# Sheet1.net
KiCad netlist of a schematic drawn in Altium Designer
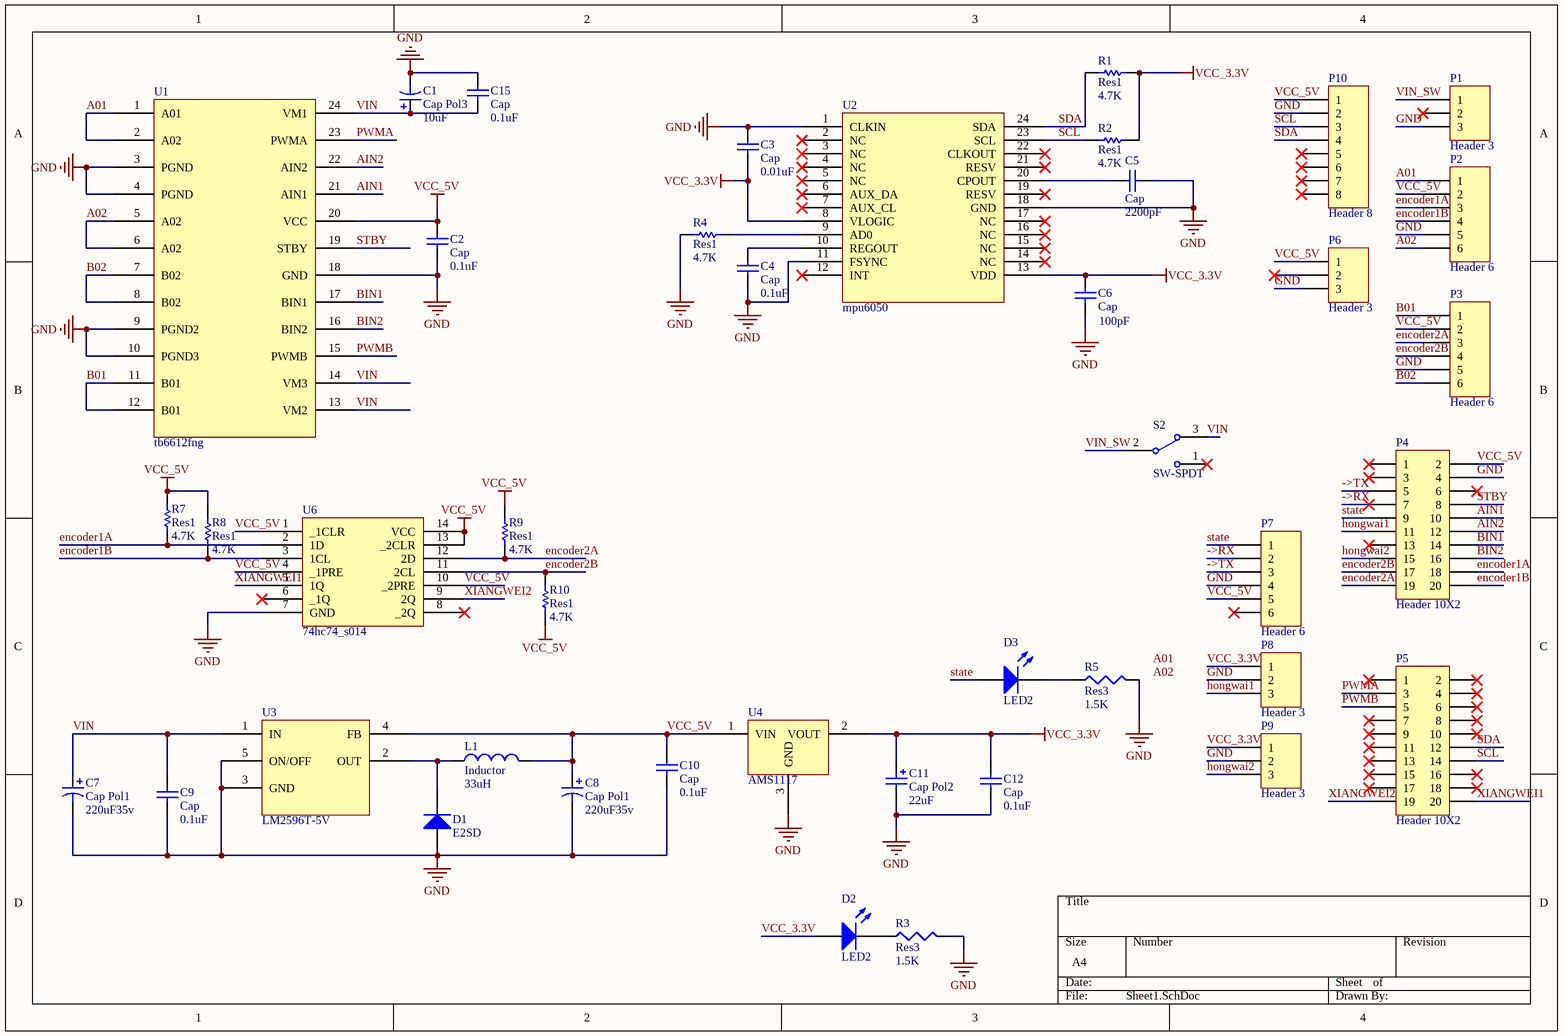
[diagram p0: Sheet1.SchDoc]

(export (version "E")
  (design (tool "Eeschema 10.0.6"))
  (components
    (comp (ref "C1")
      (value "Cap Pol3")
      (footprint "CAP POL-SMD-B")
      (description "Polarized Capacitor (Surface Mount)")
      (fields (field (name "ALTIUM_VALUE") "10uF") (field (name "PUBLISHER") "Altium Limited"))
      (libsource (lib "Miscellaneous Devices") (part "Cap Pol3"))
    )
    (comp (ref "C2")
      (value "Cap")
      (footprint "CAP-0805-手工焊接")
      (description "Capacitor")
      (fields (field (name "ALTIUM_VALUE") "0.1uF") (field (name "PUBLISHER") "Altium Limited"))
      (libsource (lib "Miscellaneous Devices") (part "Cap"))
    )
    (comp (ref "C3")
      (value "Cap")
      (footprint "CAP-0805-手工焊接")
      (description "Capacitor")
      (fields (field (name "ALTIUM_VALUE") "0.01uF") (field (name "PUBLISHER") "Altium Limited"))
      (libsource (lib "Miscellaneous Devices") (part "Cap"))
    )
    (comp (ref "C4")
      (value "Cap")
      (footprint "CAP-0805-手工焊接")
      (description "Capacitor")
      (fields (field (name "ALTIUM_VALUE") "0.1uF") (field (name "PUBLISHER") "Altium Limited"))
      (libsource (lib "Miscellaneous Devices") (part "Cap"))
    )
    (comp (ref "C5")
      (value "Cap")
      (footprint "CAP-0805-手工焊接")
      (description "Capacitor")
      (fields (field (name "ALTIUM_VALUE") "2200pF") (field (name "PUBLISHER") "Altium Limited"))
      (libsource (lib "Miscellaneous Devices") (part "Cap"))
    )
    (comp (ref "C6")
      (value "Cap")
      (footprint "CAP-0805-手工焊接")
      (description "Capacitor")
      (fields (field (name "ALTIUM_VALUE") "100pF") (field (name "PUBLISHER") "Altium Limited"))
      (libsource (lib "Miscellaneous Devices") (part "Cap"))
    )
    (comp (ref "C7")
      (value "Cap Pol1")
      (footprint "C_SMD(8x10.3)")
      (description "Polarized Capacitor (Radial)")
      (fields (field (name "ALTIUM_VALUE") "220uF35v") (field (name "PUBLISHER") "Altium Limited"))
      (libsource (lib "Miscellaneous Devices") (part "Cap Pol1"))
    )
    (comp (ref "C8")
      (value "Cap Pol1")
      (footprint "C_SMD(8x10.3)")
      (description "Polarized Capacitor (Radial)")
      (fields (field (name "ALTIUM_VALUE") "220uF35v") (field (name "PUBLISHER") "Altium Limited"))
      (libsource (lib "Miscellaneous Devices") (part "Cap Pol1"))
    )
    (comp (ref "C9")
      (value "Cap")
      (footprint "CAP-0805-手工焊接")
      (description "Capacitor")
      (fields (field (name "ALTIUM_VALUE") "0.1uF") (field (name "PUBLISHER") "Altium Limited"))
      (libsource (lib "Miscellaneous Devices") (part "Cap"))
    )
    (comp (ref "C10")
      (value "Cap")
      (footprint "CAP-0805-手工焊接")
      (description "Capacitor")
      (fields (field (name "ALTIUM_VALUE") "0.1uF") (field (name "PUBLISHER") "Altium Limited"))
      (libsource (lib "Miscellaneous Devices") (part "Cap"))
    )
    (comp (ref "C11")
      (value "Cap Pol2")
      (footprint "CAP POL-SMD-B")
      (description "Polarized Capacitor (Axial)")
      (fields (field (name "ALTIUM_VALUE") "22uF") (field (name "PUBLISHER") "Altium Limited"))
      (libsource (lib "Miscellaneous Devices") (part "Cap Pol2"))
    )
    (comp (ref "C12")
      (value "Cap")
      (footprint "CAP-0805-手工焊接")
      (description "Capacitor")
      (fields (field (name "ALTIUM_VALUE") "0.1uF") (field (name "PUBLISHER") "Altium Limited"))
      (libsource (lib "Miscellaneous Devices") (part "Cap"))
    )
    (comp (ref "C15")
      (value "Cap")
      (footprint "CAP-0805-手工焊接")
      (description "Capacitor")
      (fields (field (name "ALTIUM_VALUE") "0.1uF") (field (name "PUBLISHER") "Altium Limited"))
      (libsource (lib "Miscellaneous Devices") (part "Cap"))
    )
    (comp (ref "D1")
      (value "E2SD")
      (footprint "SMA")
      (description "Default Diode")
      (fields (field (name "PUBLISHER") "Altium Limited"))
      (libsource (lib "Miscellaneous Devices") (part "Diode"))
    )
    (comp (ref "D2")
      (value "LED2")
      (footprint "LED-0805-手工焊接")
      (description "Typical RED, GREEN, YELLOW, AMBER GaAs LED")
      (fields (field (name "PUBLISHER") "Altium Limited"))
      (libsource (lib "Miscellaneous Devices") (part "LED2"))
    )
    (comp (ref "D3")
      (value "LED2")
      (footprint "LED-0805-手工焊接")
      (description "Typical RED, GREEN, YELLOW, AMBER GaAs LED")
      (fields (field (name "PUBLISHER") "Altium Limited"))
      (libsource (lib "Miscellaneous Devices") (part "LED2"))
    )
    (comp (ref "L1")
      (value "Inductor")
      (footprint "CDRH127")
      (fields (field (name "ALTIUM_VALUE") "33uH") (field (name "PUBLISHER") "Altium Limited"))
      (libsource (lib "Miscellaneous Devices") (part "Inductor"))
    )
    (comp (ref "P1")
      (value "Header 3")
      (footprint "HDR1X3")
      (description "Header, 3-Pin")
      (fields (field (name "PUBLISHER") "Altium Limited"))
      (libsource (lib "Miscellaneous Connectors") (part "Header 3"))
    )
    (comp (ref "P2")
      (value "Header 6")
      (footprint "PH2.0 6P")
      (description "Header, 6-Pin")
      (fields (field (name "PUBLISHER") "Altium Limited"))
      (libsource (lib "Miscellaneous Connectors") (part "Header 6"))
    )
    (comp (ref "P3")
      (value "Header 6")
      (footprint "PH2.0 6P")
      (description "Header, 6-Pin")
      (fields (field (name "PUBLISHER") "Altium Limited"))
      (libsource (lib "Miscellaneous Connectors") (part "Header 6"))
    )
    (comp (ref "P4")
      (value "Header 10X2")
      (footprint "HDR2X10 - duplicate")
      (description "Header, 10-Pin, Dual row")
      (fields (field (name "PUBLISHER") "Altium Limited"))
      (libsource (lib "Miscellaneous Connectors") (part "Header 10X2"))
    )
    (comp (ref "P5")
      (value "Header 10X2")
      (footprint "HDR2X10 - duplicate")
      (description "Header, 10-Pin, Dual row")
      (fields (field (name "PUBLISHER") "Altium Limited"))
      (libsource (lib "Miscellaneous Connectors") (part "Header 10X2"))
    )
    (comp (ref "P6")
      (value "Header 3")
      (footprint "HDR1X3")
      (description "Header, 3-Pin")
      (fields (field (name "PUBLISHER") "Altium Limited"))
      (libsource (lib "Miscellaneous Connectors") (part "Header 3"))
    )
    (comp (ref "P7")
      (value "Header 6")
      (footprint "HC05 MODULE")
      (description "Header, 6-Pin")
      (fields (field (name "PUBLISHER") "Altium Limited"))
      (libsource (lib "Miscellaneous Connectors") (part "Header 6"))
    )
    (comp (ref "P8")
      (value "Header 3")
      (footprint "HDR1*3 no_edge")
      (description "Header, 3-Pin")
      (fields (field (name "PUBLISHER") "Altium Limited"))
      (libsource (lib "Miscellaneous Connectors") (part "Header 3"))
    )
    (comp (ref "P9")
      (value "Header 3")
      (footprint "HDR1*3 no_edge")
      (description "Header, 3-Pin")
      (fields (field (name "PUBLISHER") "Altium Limited"))
      (libsource (lib "Miscellaneous Connectors") (part "Header 3"))
    )
    (comp (ref "P10")
      (value "Header 8")
      (footprint "mpu6050 module")
      (description "Header, 8-Pin")
      (fields (field (name "PUBLISHER") "Altium Limited"))
      (libsource (lib "Miscellaneous Connectors") (part "Header 8"))
    )
    (comp (ref "R1")
      (value "Res1")
      (footprint "RES-0805_手工焊接")
      (description "Resistor")
      (fields (field (name "ALTIUM_VALUE") "4.7K") (field (name "PUBLISHER") "Altium Limited"))
      (libsource (lib "Miscellaneous Devices") (part "Res1"))
    )
    (comp (ref "R2")
      (value "Res1")
      (footprint "RES-0805_手工焊接")
      (description "Resistor")
      (fields (field (name "ALTIUM_VALUE") "4.7K") (field (name "PUBLISHER") "Altium Limited"))
      (libsource (lib "Miscellaneous Devices") (part "Res1"))
    )
    (comp (ref "R3")
      (value "Res3")
      (footprint "RES-0805_手工焊接")
      (description "Resistor")
      (fields (field (name "ALTIUM_VALUE") "1.5K") (field (name "PUBLISHER") "Altium Limited"))
      (libsource (lib "Miscellaneous Devices") (part "Res3"))
    )
    (comp (ref "R4")
      (value "Res1")
      (footprint "RES-0805_手工焊接")
      (description "Resistor")
      (fields (field (name "ALTIUM_VALUE") "4.7K") (field (name "PUBLISHER") "Altium Limited"))
      (libsource (lib "Miscellaneous Devices") (part "Res1"))
    )
    (comp (ref "R5")
      (value "Res3")
      (footprint "RES-0805_手工焊接")
      (description "Resistor")
      (fields (field (name "ALTIUM_VALUE") "1.5K") (field (name "PUBLISHER") "Altium Limited"))
      (libsource (lib "Miscellaneous Devices") (part "Res3"))
    )
    (comp (ref "R7")
      (value "Res1")
      (footprint "RES-0805_手工焊接")
      (description "Resistor")
      (fields (field (name "ALTIUM_VALUE") "4.7K") (field (name "PUBLISHER") "Altium Limited"))
      (libsource (lib "Miscellaneous Devices") (part "Res1"))
    )
    (comp (ref "R8")
      (value "Res1")
      (footprint "RES-0805_手工焊接")
      (description "Resistor")
      (fields (field (name "ALTIUM_VALUE") "4.7K") (field (name "PUBLISHER") "Altium Limited"))
      (libsource (lib "Miscellaneous Devices") (part "Res1"))
    )
    (comp (ref "R9")
      (value "Res1")
      (footprint "RES-0805_手工焊接")
      (description "Resistor")
      (fields (field (name "ALTIUM_VALUE") "4.7K") (field (name "PUBLISHER") "Altium Limited"))
      (libsource (lib "Miscellaneous Devices") (part "Res1"))
    )
    (comp (ref "R10")
      (value "Res1")
      (footprint "RES-0805_手工焊接")
      (description "Resistor")
      (fields (field (name "ALTIUM_VALUE") "4.7K") (field (name "PUBLISHER") "Altium Limited"))
      (libsource (lib "Miscellaneous Devices") (part "Res1"))
    )
    (comp (ref "S2")
      (value "SW-SPDT")
      (footprint "ss12d10")
      (description "SPDT Subminiature Toggle Switch, Right Angle Mounting, Vertical Actuation")
      (fields (field (name "PUBLISHER") "Altium Limited"))
      (libsource (lib "Miscellaneous Devices") (part "SW-SPDT"))
    )
    (comp (ref "U1")
      (value "tb6612fng")
      (footprint "tb6612fng - duplicate")
      (libsource (lib "Schlib1") (part "tb6612fng"))
    )
    (comp (ref "U2") (value "mpu6050") (footprint "QFN-24") (libsource (lib "Schlib1") (part "mpu6050")))
    (comp (ref "U3")
      (value "LM2596T-5V")
      (footprint "TO-263-5 - TYPE1")
      (libsource (lib "Schlib1") (part "LM2596T-5V"))
    )
    (comp (ref "U4") (value "AMS1117") (footprint "SOT-223") (libsource (lib "Schlib1") (part "AMS1117")))
    (comp (ref "U6")
      (value "74hc74_s014")
      (footprint "74HC74D_SOP14")
      (libsource (lib "Schlib1") (part "74hc74_s014"))
    )
  )
  (nets
    (net (code "1") (name "/->RX") (class "Default")
      (node (ref "P4") (pin "7") (pinfunction "7_7") (pintype "passive"))
      (node (ref "P7") (pin "2") (pinfunction "2_2") (pintype "passive"))
    )
    (net (code "2") (name "/->TX") (class "Default")
      (node (ref "P4") (pin "5") (pinfunction "5_5") (pintype "passive"))
      (node (ref "P7") (pin "3") (pinfunction "3_3") (pintype "passive"))
    )
    (net (code "3") (name "/A01") (class "Default")
      (node (ref "P2") (pin "1") (pinfunction "1_1") (pintype "passive"))
      (node (ref "U1") (pin "1") (pinfunction "A01_1") (pintype "passive"))
      (node (ref "U1") (pin "2") (pinfunction "A02_2") (pintype "passive"))
    )
    (net (code "4") (name "/A02") (class "Default")
      (node (ref "P2") (pin "6") (pinfunction "6_6") (pintype "passive"))
      (node (ref "U1") (pin "5") (pinfunction "A02_5") (pintype "passive"))
      (node (ref "U1") (pin "6") (pinfunction "A02_6") (pintype "passive"))
    )
    (net (code "5") (name "/AIN1") (class "Default")
      (node (ref "P4") (pin "10") (pinfunction "10_10") (pintype "passive"))
      (node (ref "U1") (pin "21") (pinfunction "AIN1_21") (pintype "passive"))
    )
    (net (code "6") (name "/AIN2") (class "Default")
      (node (ref "P4") (pin "12") (pinfunction "12_12") (pintype "passive"))
      (node (ref "U1") (pin "22") (pinfunction "AIN2_22") (pintype "passive"))
    )
    (net (code "7") (name "/B01") (class "Default")
      (node (ref "P3") (pin "1") (pinfunction "1_1") (pintype "passive"))
      (node (ref "U1") (pin "11") (pinfunction "B01_11") (pintype "passive"))
      (node (ref "U1") (pin "12") (pinfunction "B01_12") (pintype "passive"))
    )
    (net (code "8") (name "/B02") (class "Default")
      (node (ref "P3") (pin "6") (pinfunction "6_6") (pintype "passive"))
      (node (ref "U1") (pin "7") (pinfunction "B02_7") (pintype "passive"))
      (node (ref "U1") (pin "8") (pinfunction "B02_8") (pintype "passive"))
    )
    (net (code "9") (name "/BIN1") (class "Default")
      (node (ref "P4") (pin "14") (pinfunction "14_14") (pintype "passive"))
      (node (ref "U1") (pin "17") (pinfunction "BIN1_17") (pintype "passive"))
    )
    (net (code "10") (name "/BIN2") (class "Default")
      (node (ref "P4") (pin "16") (pinfunction "16_16") (pintype "passive"))
      (node (ref "U1") (pin "16") (pinfunction "BIN2_16") (pintype "passive"))
    )
    (net (code "11") (name "/PWMA") (class "Default")
      (node (ref "P5") (pin "3") (pinfunction "3_3") (pintype "passive"))
      (node (ref "U1") (pin "23") (pinfunction "PWMA_23") (pintype "passive"))
    )
    (net (code "12") (name "/PWMB") (class "Default")
      (node (ref "P5") (pin "5") (pinfunction "5_5") (pintype "passive"))
      (node (ref "U1") (pin "15") (pinfunction "PWMB_15") (pintype "passive"))
    )
    (net (code "13") (name "/SCL") (class "Default")
      (node (ref "P10") (pin "3") (pinfunction "3_3") (pintype "passive"))
      (node (ref "P5") (pin "14") (pinfunction "14_14") (pintype "passive"))
      (node (ref "R2") (pin "1") (pinfunction "1_1") (pintype "passive"))
      (node (ref "U2") (pin "23") (pinfunction "SCL_23") (pintype "passive"))
    )
    (net (code "14") (name "/SDA") (class "Default")
      (node (ref "P10") (pin "4") (pinfunction "4_4") (pintype "passive"))
      (node (ref "P5") (pin "12") (pinfunction "12_12") (pintype "passive"))
      (node (ref "R1") (pin "1") (pinfunction "1_1") (pintype "passive"))
      (node (ref "U2") (pin "24") (pinfunction "SDA_24") (pintype "passive"))
    )
    (net (code "15") (name "/STBY") (class "Default")
      (node (ref "P4") (pin "8") (pinfunction "8_8") (pintype "passive"))
      (node (ref "U1") (pin "19") (pinfunction "STBY_19") (pintype "passive"))
    )
    (net (code "16") (name "/VIN") (class "Default")
      (node (ref "C1") (pin "1") (pinfunction "1_1") (pintype "passive"))
      (node (ref "C15") (pin "1") (pinfunction "1_1") (pintype "passive"))
      (node (ref "C7") (pin "1") (pinfunction "1_1") (pintype "passive"))
      (node (ref "C9") (pin "2") (pinfunction "2_2") (pintype "passive"))
      (node (ref "S2") (pin "3") (pinfunction "3_3") (pintype "passive"))
      (node (ref "U1") (pin "13") (pinfunction "VM2_13") (pintype "passive"))
      (node (ref "U1") (pin "14") (pinfunction "VM3_14") (pintype "passive"))
      (node (ref "U1") (pin "24") (pinfunction "VM1_24") (pintype "passive"))
      (node (ref "U3") (pin "1") (pinfunction "IN_1") (pintype "passive"))
    )
    (net (code "17") (name "/VIN_SW") (class "Default")
      (node (ref "P1") (pin "1") (pinfunction "1_1") (pintype "passive"))
      (node (ref "S2") (pin "2") (pinfunction "2_2") (pintype "passive"))
    )
    (net (code "18") (name "/XIANGWEI1") (class "Default")
      (node (ref "P5") (pin "20") (pinfunction "20_20") (pintype "passive"))
      (node (ref "U6") (pin "5") (pinfunction "1Q_5") (pintype "passive"))
    )
    (net (code "19") (name "/XIANGWEI2") (class "Default")
      (node (ref "P5") (pin "19") (pinfunction "19_19") (pintype "passive"))
      (node (ref "U6") (pin "9") (pinfunction "2Q_9") (pintype "passive"))
    )
    (net (code "20") (name "/encoder1A") (class "Default")
      (node (ref "P2") (pin "3") (pinfunction "3_3") (pintype "passive"))
      (node (ref "P4") (pin "18") (pinfunction "18_18") (pintype "passive"))
      (node (ref "R7") (pin "2") (pinfunction "2_2") (pintype "passive"))
      (node (ref "U6") (pin "2") (pinfunction "1D_2") (pintype "passive"))
    )
    (net (code "21") (name "/encoder1B") (class "Default")
      (node (ref "P2") (pin "4") (pinfunction "4_4") (pintype "passive"))
      (node (ref "P4") (pin "20") (pinfunction "20_20") (pintype "passive"))
      (node (ref "R8") (pin "2") (pinfunction "2_2") (pintype "passive"))
      (node (ref "U6") (pin "3") (pinfunction "1CL_3") (pintype "passive"))
    )
    (net (code "22") (name "/encoder2A") (class "Default")
      (node (ref "P3") (pin "3") (pinfunction "3_3") (pintype "passive"))
      (node (ref "P4") (pin "19") (pinfunction "19_19") (pintype "passive"))
      (node (ref "R9") (pin "2") (pinfunction "2_2") (pintype "passive"))
      (node (ref "U6") (pin "12") (pinfunction "2D_12") (pintype "passive"))
    )
    (net (code "23") (name "/encoder2B") (class "Default")
      (node (ref "P3") (pin "4") (pinfunction "4_4") (pintype "passive"))
      (node (ref "P4") (pin "17") (pinfunction "17_17") (pintype "passive"))
      (node (ref "R10") (pin "1") (pinfunction "1_1") (pintype "passive"))
      (node (ref "U6") (pin "11") (pinfunction "2CL_11") (pintype "passive"))
    )
    (net (code "24") (name "/hongwai1") (class "Default")
      (node (ref "P4") (pin "11") (pinfunction "11_11") (pintype "passive"))
      (node (ref "P8") (pin "3") (pinfunction "3_3") (pintype "passive"))
    )
    (net (code "25") (name "/hongwai2") (class "Default")
      (node (ref "P4") (pin "15") (pinfunction "15_15") (pintype "passive"))
      (node (ref "P9") (pin "3") (pinfunction "3_3") (pintype "passive"))
    )
    (net (code "26") (name "/state") (class "Default")
      (node (ref "D3") (pin "1") (pinfunction "A_1") (pintype "passive"))
      (node (ref "P4") (pin "9") (pinfunction "9_9") (pintype "passive"))
      (node (ref "P7") (pin "1") (pinfunction "1_1") (pintype "passive"))
    )
    (net (code "27") (name "GND") (class "Default")
      (node (ref "C1") (pin "2") (pinfunction "2_2") (pintype "passive"))
      (node (ref "C10") (pin "1") (pinfunction "1_1") (pintype "passive"))
      (node (ref "C11") (pin "2") (pinfunction "2_2") (pintype "passive"))
      (node (ref "C12") (pin "1") (pinfunction "1_1") (pintype "passive"))
      (node (ref "C15") (pin "2") (pinfunction "2_2") (pintype "passive"))
      (node (ref "C2") (pin "1") (pinfunction "1_1") (pintype "passive"))
      (node (ref "C3") (pin "2") (pinfunction "2_2") (pintype "passive"))
      (node (ref "C4") (pin "1") (pinfunction "1_1") (pintype "passive"))
      (node (ref "C5") (pin "1") (pinfunction "1_1") (pintype "passive"))
      (node (ref "C6") (pin "1") (pinfunction "1_1") (pintype "passive"))
      (node (ref "C7") (pin "2") (pinfunction "2_2") (pintype "passive"))
      (node (ref "C8") (pin "2") (pinfunction "2_2") (pintype "passive"))
      (node (ref "C9") (pin "1") (pinfunction "1_1") (pintype "passive"))
      (node (ref "D1") (pin "1") (pinfunction "A_1") (pintype "passive"))
      (node (ref "P1") (pin "3") (pinfunction "3_3") (pintype "passive"))
      (node (ref "P10") (pin "2") (pinfunction "2_2") (pintype "passive"))
      (node (ref "P2") (pin "5") (pinfunction "5_5") (pintype "passive"))
      (node (ref "P3") (pin "5") (pinfunction "5_5") (pintype "passive"))
      (node (ref "P4") (pin "4") (pinfunction "4_4") (pintype "passive"))
      (node (ref "P6") (pin "3") (pinfunction "3_3") (pintype "passive"))
      (node (ref "P7") (pin "4") (pinfunction "4_4") (pintype "passive"))
      (node (ref "P8") (pin "2") (pinfunction "2_2") (pintype "passive"))
      (node (ref "P9") (pin "2") (pinfunction "2_2") (pintype "passive"))
      (node (ref "R3") (pin "2") (pinfunction "2_2") (pintype "passive"))
      (node (ref "R4") (pin "1") (pinfunction "1_1") (pintype "passive"))
      (node (ref "R5") (pin "2") (pinfunction "2_2") (pintype "passive"))
      (node (ref "U1") (pin "10") (pinfunction "PGND3_10") (pintype "passive"))
      (node (ref "U1") (pin "18") (pinfunction "GND_18") (pintype "passive"))
      (node (ref "U1") (pin "3") (pinfunction "PGND_3") (pintype "passive"))
      (node (ref "U1") (pin "4") (pinfunction "PGND_4") (pintype "passive"))
      (node (ref "U1") (pin "9") (pinfunction "PGND2_9") (pintype "passive"))
      (node (ref "U2") (pin "1") (pinfunction "CLKIN_1") (pintype "passive"))
      (node (ref "U2") (pin "11") (pinfunction "FSYNC_11") (pintype "passive"))
      (node (ref "U2") (pin "18") (pinfunction "GND_18") (pintype "passive"))
      (node (ref "U3") (pin "3") (pinfunction "GND_3") (pintype "passive"))
      (node (ref "U3") (pin "5") (pinfunction "ON/OFF_5") (pintype "passive"))
      (node (ref "U4") (pin "3") (pinfunction "GND_3") (pintype "passive"))
      (node (ref "U6") (pin "7") (pinfunction "GND_7") (pintype "passive"))
    )
    (net (code "28") (name "Net-(D1-K)") (class "Default")
      (node (ref "D1") (pin "2") (pinfunction "K_2") (pintype "passive"))
      (node (ref "L1") (pin "1") (pinfunction "1_1") (pintype "passive"))
      (node (ref "U3") (pin "2") (pinfunction "OUT_2") (pintype "passive"))
    )
    (net (code "29") (name "Net-(D2-K)") (class "Default")
      (node (ref "D2") (pin "2") (pinfunction "K_2") (pintype "passive"))
      (node (ref "R3") (pin "1") (pinfunction "1_1") (pintype "passive"))
    )
    (net (code "30") (name "Net-(D3-K)") (class "Default")
      (node (ref "D3") (pin "2") (pinfunction "K_2") (pintype "passive"))
      (node (ref "R5") (pin "1") (pinfunction "1_1") (pintype "passive"))
    )
    (net (code "31") (name "Net-(U2-AD0)") (class "Default")
      (node (ref "R4") (pin "2") (pinfunction "2_2") (pintype "passive"))
      (node (ref "U2") (pin "9") (pinfunction "AD0_9") (pintype "passive"))
    )
    (net (code "32") (name "Net-(U2-CPOUT)") (class "Default")
      (node (ref "C5") (pin "2") (pinfunction "2_2") (pintype "passive"))
      (node (ref "U2") (pin "20") (pinfunction "CPOUT_20") (pintype "passive"))
    )
    (net (code "33") (name "Net-(U2-REGOUT)") (class "Default")
      (node (ref "C4") (pin "2") (pinfunction "2_2") (pintype "passive"))
      (node (ref "U2") (pin "10") (pinfunction "REGOUT_10") (pintype "passive"))
    )
    (net (code "34") (name "VCC_3.3V") (class "Default")
      (node (ref "C11") (pin "1") (pinfunction "1_1") (pintype "passive"))
      (node (ref "C12") (pin "2") (pinfunction "2_2") (pintype "passive"))
      (node (ref "C3") (pin "1") (pinfunction "1_1") (pintype "passive"))
      (node (ref "C6") (pin "2") (pinfunction "2_2") (pintype "passive"))
      (node (ref "D2") (pin "1") (pinfunction "A_1") (pintype "passive"))
      (node (ref "P8") (pin "1") (pinfunction "1_1") (pintype "passive"))
      (node (ref "P9") (pin "1") (pinfunction "1_1") (pintype "passive"))
      (node (ref "R1") (pin "2") (pinfunction "2_2") (pintype "passive"))
      (node (ref "R2") (pin "2") (pinfunction "2_2") (pintype "passive"))
      (node (ref "U2") (pin "13") (pinfunction "VDD_13") (pintype "passive"))
      (node (ref "U2") (pin "8") (pinfunction "VLOGIC_8") (pintype "passive"))
      (node (ref "U4") (pin "2") (pinfunction "VOUT_2") (pintype "passive"))
    )
    (net (code "35") (name "VCC_5V") (class "Default")
      (node (ref "C10") (pin "2") (pinfunction "2_2") (pintype "passive"))
      (node (ref "C2") (pin "2") (pinfunction "2_2") (pintype "passive"))
      (node (ref "C8") (pin "1") (pinfunction "1_1") (pintype "passive"))
      (node (ref "L1") (pin "2") (pinfunction "2_2") (pintype "passive"))
      (node (ref "P10") (pin "1") (pinfunction "1_1") (pintype "passive"))
      (node (ref "P2") (pin "2") (pinfunction "2_2") (pintype "passive"))
      (node (ref "P3") (pin "2") (pinfunction "2_2") (pintype "passive"))
      (node (ref "P4") (pin "2") (pinfunction "2_2") (pintype "passive"))
      (node (ref "P6") (pin "1") (pinfunction "1_1") (pintype "passive"))
      (node (ref "P7") (pin "5") (pinfunction "5_5") (pintype "passive"))
      (node (ref "R10") (pin "2") (pinfunction "2_2") (pintype "passive"))
      (node (ref "R7") (pin "1") (pinfunction "1_1") (pintype "passive"))
      (node (ref "R8") (pin "1") (pinfunction "1_1") (pintype "passive"))
      (node (ref "R9") (pin "1") (pinfunction "1_1") (pintype "passive"))
      (node (ref "U1") (pin "20") (pinfunction "VCC_20") (pintype "passive"))
      (node (ref "U3") (pin "4") (pinfunction "FB_4") (pintype "passive"))
      (node (ref "U4") (pin "1") (pinfunction "VIN_1") (pintype "passive"))
      (node (ref "U6") (pin "1") (pinfunction "_1CLR_1") (pintype "passive"))
      (node (ref "U6") (pin "10") (pinfunction "_2PRE_10") (pintype "passive"))
      (node (ref "U6") (pin "13") (pinfunction "_2CLR_13") (pintype "passive"))
      (node (ref "U6") (pin "14") (pinfunction "VCC_14") (pintype "passive"))
      (node (ref "U6") (pin "4") (pinfunction "_1PRE_4") (pintype "passive"))
    )
    (net (code "36") (name "unconnected-(P1-Pad2)") (class "Default")
      (node (ref "P1") (pin "2") (pinfunction "2_2") (pintype "passive+no_connect"))
    )
    (net (code "37") (name "unconnected-(P4-Pad1)") (class "Default")
      (node (ref "P4") (pin "1") (pinfunction "1_1") (pintype "passive+no_connect"))
    )
    (net (code "38") (name "unconnected-(P4-Pad3)") (class "Default")
      (node (ref "P4") (pin "3") (pinfunction "3_3") (pintype "passive+no_connect"))
    )
    (net (code "39") (name "unconnected-(P4-Pad6)") (class "Default")
      (node (ref "P4") (pin "6") (pinfunction "6_6") (pintype "passive+no_connect"))
    )
    (net (code "40") (name "unconnected-(P4-Pad13)") (class "Default")
      (node (ref "P4") (pin "13") (pinfunction "13_13") (pintype "passive+no_connect"))
    )
    (net (code "41") (name "unconnected-(P5-Pad1)") (class "Default")
      (node (ref "P5") (pin "1") (pinfunction "1_1") (pintype "passive+no_connect"))
    )
    (net (code "42") (name "unconnected-(P5-Pad2)") (class "Default")
      (node (ref "P5") (pin "2") (pinfunction "2_2") (pintype "passive+no_connect"))
    )
    (net (code "43") (name "unconnected-(P5-Pad4)") (class "Default")
      (node (ref "P5") (pin "4") (pinfunction "4_4") (pintype "passive+no_connect"))
    )
    (net (code "44") (name "unconnected-(P5-Pad6)") (class "Default")
      (node (ref "P5") (pin "6") (pinfunction "6_6") (pintype "passive+no_connect"))
    )
    (net (code "45") (name "unconnected-(P5-Pad7)") (class "Default")
      (node (ref "P5") (pin "7") (pinfunction "7_7") (pintype "passive+no_connect"))
    )
    (net (code "46") (name "unconnected-(P5-Pad8)") (class "Default")
      (node (ref "P5") (pin "8") (pinfunction "8_8") (pintype "passive+no_connect"))
    )
    (net (code "47") (name "unconnected-(P5-Pad9)") (class "Default")
      (node (ref "P5") (pin "9") (pinfunction "9_9") (pintype "passive+no_connect"))
    )
    (net (code "48") (name "unconnected-(P5-Pad10)") (class "Default")
      (node (ref "P5") (pin "10") (pinfunction "10_10") (pintype "passive+no_connect"))
    )
    (net (code "49") (name "unconnected-(P5-Pad11)") (class "Default")
      (node (ref "P5") (pin "11") (pinfunction "11_11") (pintype "passive+no_connect"))
    )
    (net (code "50") (name "unconnected-(P5-Pad13)") (class "Default")
      (node (ref "P5") (pin "13") (pinfunction "13_13") (pintype "passive+no_connect"))
    )
    (net (code "51") (name "unconnected-(P5-Pad15)") (class "Default")
      (node (ref "P5") (pin "15") (pinfunction "15_15") (pintype "passive+no_connect"))
    )
    (net (code "52") (name "unconnected-(P5-Pad16)") (class "Default")
      (node (ref "P5") (pin "16") (pinfunction "16_16") (pintype "passive+no_connect"))
    )
    (net (code "53") (name "unconnected-(P5-Pad17)") (class "Default")
      (node (ref "P5") (pin "17") (pinfunction "17_17") (pintype "passive+no_connect"))
    )
    (net (code "54") (name "unconnected-(P5-Pad18)") (class "Default")
      (node (ref "P5") (pin "18") (pinfunction "18_18") (pintype "passive+no_connect"))
    )
    (net (code "55") (name "unconnected-(P6-Pad2)") (class "Default")
      (node (ref "P6") (pin "2") (pinfunction "2_2") (pintype "passive+no_connect"))
    )
    (net (code "56") (name "unconnected-(P7-Pad6)") (class "Default")
      (node (ref "P7") (pin "6") (pinfunction "6_6") (pintype "passive+no_connect"))
    )
    (net (code "57") (name "unconnected-(P10-Pad5)") (class "Default")
      (node (ref "P10") (pin "5") (pinfunction "5_5") (pintype "passive+no_connect"))
    )
    (net (code "58") (name "unconnected-(P10-Pad6)") (class "Default")
      (node (ref "P10") (pin "6") (pinfunction "6_6") (pintype "passive+no_connect"))
    )
    (net (code "59") (name "unconnected-(P10-Pad7)") (class "Default")
      (node (ref "P10") (pin "7") (pinfunction "7_7") (pintype "passive+no_connect"))
    )
    (net (code "60") (name "unconnected-(P10-Pad8)") (class "Default")
      (node (ref "P10") (pin "8") (pinfunction "8_8") (pintype "passive+no_connect"))
    )
    (net (code "61") (name "unconnected-(S2-Pad1)") (class "Default")
      (node (ref "S2") (pin "1") (pinfunction "1_1") (pintype "passive+no_connect"))
    )
    (net (code "62") (name "unconnected-(U2-AUX_CL-Pad7)") (class "Default")
      (node (ref "U2") (pin "7") (pinfunction "AUX_CL_7") (pintype "passive+no_connect"))
    )
    (net (code "63") (name "unconnected-(U2-AUX_DA-Pad6)") (class "Default")
      (node (ref "U2") (pin "6") (pinfunction "AUX_DA_6") (pintype "passive+no_connect"))
    )
    (net (code "64") (name "unconnected-(U2-CLKOUT-Pad22)") (class "Default")
      (node (ref "U2") (pin "22") (pinfunction "CLKOUT_22") (pintype "passive+no_connect"))
    )
    (net (code "65") (name "unconnected-(U2-INT-Pad12)") (class "Default")
      (node (ref "U2") (pin "12") (pinfunction "INT_12") (pintype "passive+no_connect"))
    )
    (net (code "66") (name "unconnected-(U2-NC-Pad2)") (class "Default")
      (node (ref "U2") (pin "2") (pinfunction "NC_2") (pintype "passive+no_connect"))
    )
    (net (code "67") (name "unconnected-(U2-NC-Pad3)") (class "Default")
      (node (ref "U2") (pin "3") (pinfunction "NC_3") (pintype "passive+no_connect"))
    )
    (net (code "68") (name "unconnected-(U2-NC-Pad4)") (class "Default")
      (node (ref "U2") (pin "4") (pinfunction "NC_4") (pintype "passive+no_connect"))
    )
    (net (code "69") (name "unconnected-(U2-NC-Pad5)") (class "Default")
      (node (ref "U2") (pin "5") (pinfunction "NC_5") (pintype "passive+no_connect"))
    )
    (net (code "70") (name "unconnected-(U2-NC-Pad14)") (class "Default")
      (node (ref "U2") (pin "14") (pinfunction "NC_14") (pintype "passive+no_connect"))
    )
    (net (code "71") (name "unconnected-(U2-NC-Pad15)") (class "Default")
      (node (ref "U2") (pin "15") (pinfunction "NC_15") (pintype "passive+no_connect"))
    )
    (net (code "72") (name "unconnected-(U2-NC-Pad16)") (class "Default")
      (node (ref "U2") (pin "16") (pinfunction "NC_16") (pintype "passive+no_connect"))
    )
    (net (code "73") (name "unconnected-(U2-NC-Pad17)") (class "Default")
      (node (ref "U2") (pin "17") (pinfunction "NC_17") (pintype "passive+no_connect"))
    )
    (net (code "74") (name "unconnected-(U2-RESV-Pad19)") (class "Default")
      (node (ref "U2") (pin "19") (pinfunction "RESV_19") (pintype "passive+no_connect"))
    )
    (net (code "75") (name "unconnected-(U2-RESV-Pad21)") (class "Default")
      (node (ref "U2") (pin "21") (pinfunction "RESV_21") (pintype "passive+no_connect"))
    )
    (net (code "76") (name "unconnected-(U6-_1Q-Pad6)") (class "Default")
      (node (ref "U6") (pin "6") (pinfunction "_1Q_6") (pintype "passive+no_connect"))
    )
    (net (code "77") (name "unconnected-(U6-_2Q-Pad8)") (class "Default")
      (node (ref "U6") (pin "8") (pinfunction "_2Q_8") (pintype "passive+no_connect"))
    )
  )
)
